# fp.net
KiCad netlist of a schematic drawn in EAGLE
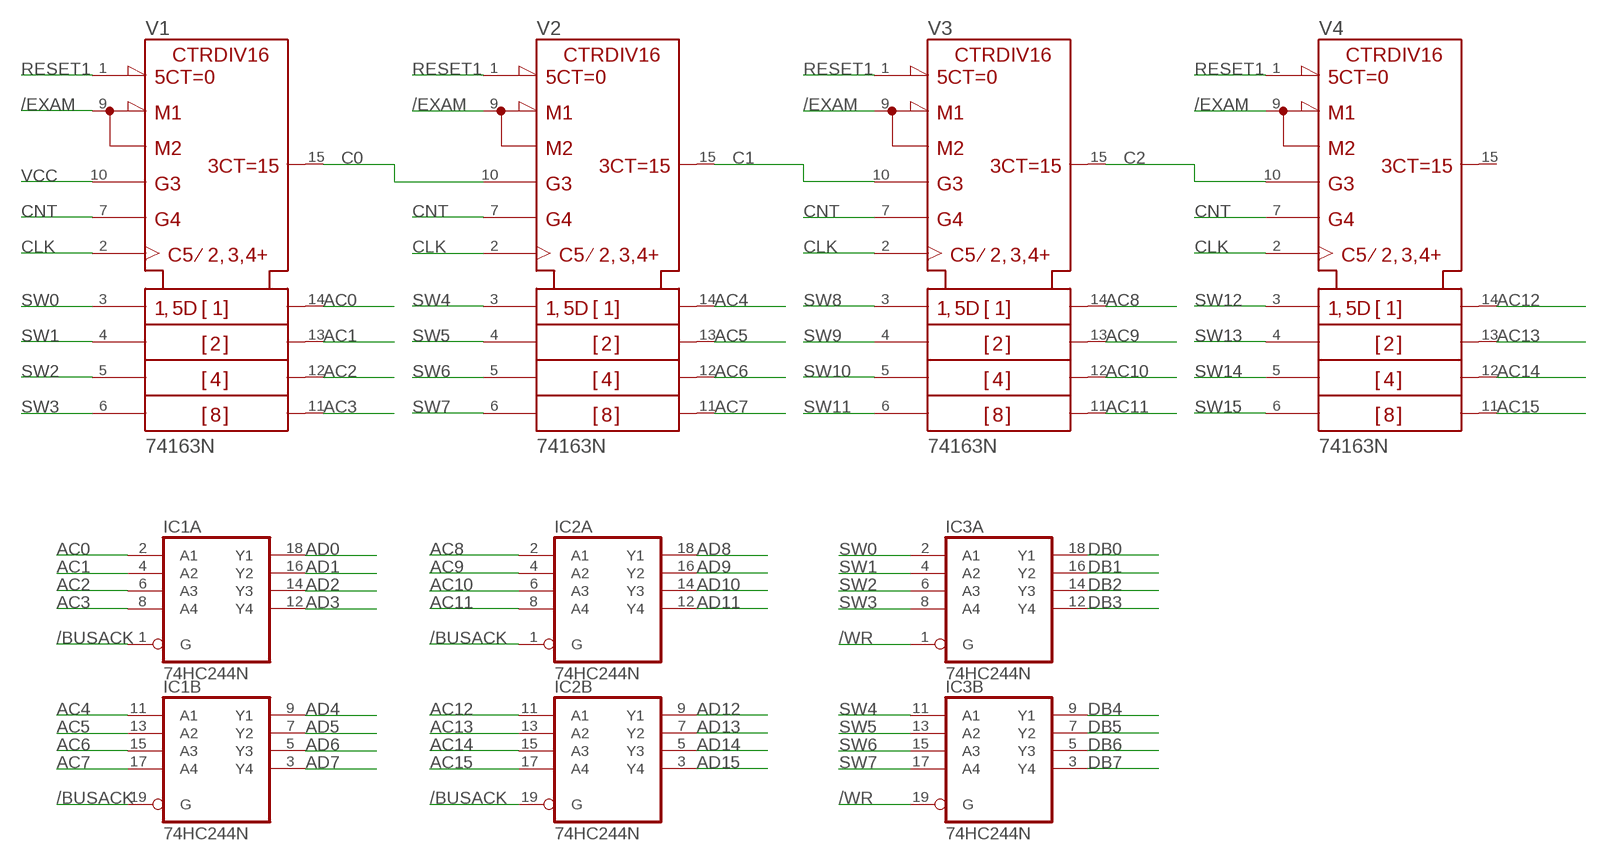
[diagram p0: schematic, sheet 1]

(export (version "E")
  (design (tool "Eeschema 10.0.6"))
  (components
    (comp (ref "IC1")
      (value "74HC244N")
      (footprint "eagle-import:DIL20")
      (libsource (lib "eagle-import") (part "74244NHC"))
    )
    (comp (ref "IC2")
      (value "74HC244N")
      (footprint "eagle-import:DIL20")
      (libsource (lib "eagle-import") (part "74244NHC"))
    )
    (comp (ref "IC3")
      (value "74HC244N")
      (footprint "eagle-import:DIL20")
      (libsource (lib "eagle-import") (part "74244NHC"))
    )
    (comp (ref "V1")
      (value "74163N")
      (footprint "eagle-import:DIL16")
      (libsource (lib "eagle-import") (part "74163N"))
    )
    (comp (ref "V2")
      (value "74163N")
      (footprint "eagle-import:DIL16")
      (libsource (lib "eagle-import") (part "74163N"))
    )
    (comp (ref "V3")
      (value "74163N")
      (footprint "eagle-import:DIL16")
      (libsource (lib "eagle-import") (part "74163N"))
    )
    (comp (ref "V4")
      (value "74163N")
      (footprint "eagle-import:DIL16")
      (libsource (lib "eagle-import") (part "74163N"))
    )
  )
  (nets
    (net (code "1") (name "/AC0") (class "Default")
      (node (ref "IC1") (pin "2") (pinfunction "A1_2") (pintype "input"))
      (node (ref "V1") (pin "14") (pinfunction "QA_14") (pintype "output"))
    )
    (net (code "2") (name "/AC1") (class "Default")
      (node (ref "IC1") (pin "4") (pinfunction "A2_4") (pintype "input"))
      (node (ref "V1") (pin "13") (pinfunction "QB_13") (pintype "output"))
    )
    (net (code "3") (name "/AC2") (class "Default")
      (node (ref "IC1") (pin "6") (pinfunction "A3_6") (pintype "input"))
      (node (ref "V1") (pin "12") (pinfunction "QC_12") (pintype "output"))
    )
    (net (code "4") (name "/AC3") (class "Default")
      (node (ref "IC1") (pin "8") (pinfunction "A4_8") (pintype "input"))
      (node (ref "V1") (pin "11") (pinfunction "QD_11") (pintype "output"))
    )
    (net (code "5") (name "/AC4") (class "Default")
      (node (ref "IC1") (pin "11") (pinfunction "A1_11") (pintype "input"))
      (node (ref "V2") (pin "14") (pinfunction "QA_14") (pintype "output"))
    )
    (net (code "6") (name "/AC5") (class "Default")
      (node (ref "IC1") (pin "13") (pinfunction "A2_13") (pintype "input"))
      (node (ref "V2") (pin "13") (pinfunction "QB_13") (pintype "output"))
    )
    (net (code "7") (name "/AC6") (class "Default")
      (node (ref "IC1") (pin "15") (pinfunction "A3_15") (pintype "input"))
      (node (ref "V2") (pin "12") (pinfunction "QC_12") (pintype "output"))
    )
    (net (code "8") (name "/AC7") (class "Default")
      (node (ref "IC1") (pin "17") (pinfunction "A4_17") (pintype "input"))
      (node (ref "V2") (pin "11") (pinfunction "QD_11") (pintype "output"))
    )
    (net (code "9") (name "/AC8") (class "Default")
      (node (ref "IC2") (pin "2") (pinfunction "A1_2") (pintype "input"))
      (node (ref "V3") (pin "14") (pinfunction "QA_14") (pintype "output"))
    )
    (net (code "10") (name "/AC9") (class "Default")
      (node (ref "IC2") (pin "4") (pinfunction "A2_4") (pintype "input"))
      (node (ref "V3") (pin "13") (pinfunction "QB_13") (pintype "output"))
    )
    (net (code "11") (name "/AC10") (class "Default")
      (node (ref "IC2") (pin "6") (pinfunction "A3_6") (pintype "input"))
      (node (ref "V3") (pin "12") (pinfunction "QC_12") (pintype "output"))
    )
    (net (code "12") (name "/AC11") (class "Default")
      (node (ref "IC2") (pin "8") (pinfunction "A4_8") (pintype "input"))
      (node (ref "V3") (pin "11") (pinfunction "QD_11") (pintype "output"))
    )
    (net (code "13") (name "/AC12") (class "Default")
      (node (ref "IC2") (pin "11") (pinfunction "A1_11") (pintype "input"))
      (node (ref "V4") (pin "14") (pinfunction "QA_14") (pintype "output"))
    )
    (net (code "14") (name "/AC13") (class "Default")
      (node (ref "IC2") (pin "13") (pinfunction "A2_13") (pintype "input"))
      (node (ref "V4") (pin "13") (pinfunction "QB_13") (pintype "output"))
    )
    (net (code "15") (name "/AC14") (class "Default")
      (node (ref "IC2") (pin "15") (pinfunction "A3_15") (pintype "input"))
      (node (ref "V4") (pin "12") (pinfunction "QC_12") (pintype "output"))
    )
    (net (code "16") (name "/AC15") (class "Default")
      (node (ref "IC2") (pin "17") (pinfunction "A4_17") (pintype "input"))
      (node (ref "V4") (pin "11") (pinfunction "QD_11") (pintype "output"))
    )
    (net (code "17") (name "/AD0") (class "Default")
      (node (ref "IC1") (pin "18") (pinfunction "Y1_18") (pintype "tri_state"))
    )
    (net (code "18") (name "/AD1") (class "Default")
      (node (ref "IC1") (pin "16") (pinfunction "Y2_16") (pintype "tri_state"))
    )
    (net (code "19") (name "/AD2") (class "Default")
      (node (ref "IC1") (pin "14") (pinfunction "Y3_14") (pintype "tri_state"))
    )
    (net (code "20") (name "/AD3") (class "Default")
      (node (ref "IC1") (pin "12") (pinfunction "Y4_12") (pintype "tri_state"))
    )
    (net (code "21") (name "/AD4") (class "Default")
      (node (ref "IC1") (pin "9") (pinfunction "Y1_9") (pintype "tri_state"))
    )
    (net (code "22") (name "/AD5") (class "Default")
      (node (ref "IC1") (pin "7") (pinfunction "Y2_7") (pintype "tri_state"))
    )
    (net (code "23") (name "/AD6") (class "Default")
      (node (ref "IC1") (pin "5") (pinfunction "Y3_5") (pintype "tri_state"))
    )
    (net (code "24") (name "/AD7") (class "Default")
      (node (ref "IC1") (pin "3") (pinfunction "Y4_3") (pintype "tri_state"))
    )
    (net (code "25") (name "/AD8") (class "Default")
      (node (ref "IC2") (pin "18") (pinfunction "Y1_18") (pintype "tri_state"))
    )
    (net (code "26") (name "/AD9") (class "Default")
      (node (ref "IC2") (pin "16") (pinfunction "Y2_16") (pintype "tri_state"))
    )
    (net (code "27") (name "/AD10") (class "Default")
      (node (ref "IC2") (pin "14") (pinfunction "Y3_14") (pintype "tri_state"))
    )
    (net (code "28") (name "/AD11") (class "Default")
      (node (ref "IC2") (pin "12") (pinfunction "Y4_12") (pintype "tri_state"))
    )
    (net (code "29") (name "/AD12") (class "Default")
      (node (ref "IC2") (pin "9") (pinfunction "Y1_9") (pintype "tri_state"))
    )
    (net (code "30") (name "/AD13") (class "Default")
      (node (ref "IC2") (pin "7") (pinfunction "Y2_7") (pintype "tri_state"))
    )
    (net (code "31") (name "/AD14") (class "Default")
      (node (ref "IC2") (pin "5") (pinfunction "Y3_5") (pintype "tri_state"))
    )
    (net (code "32") (name "/AD15") (class "Default")
      (node (ref "IC2") (pin "3") (pinfunction "Y4_3") (pintype "tri_state"))
    )
    (net (code "33") (name "/C0") (class "Default")
      (node (ref "V1") (pin "15") (pinfunction "RCO_15") (pintype "output"))
      (node (ref "V2") (pin "10") (pinfunction "ENT_10") (pintype "input"))
    )
    (net (code "34") (name "/C1") (class "Default")
      (node (ref "V2") (pin "15") (pinfunction "RCO_15") (pintype "output"))
      (node (ref "V3") (pin "10") (pinfunction "ENT_10") (pintype "input"))
    )
    (net (code "35") (name "/C2") (class "Default")
      (node (ref "V3") (pin "15") (pinfunction "RCO_15") (pintype "output"))
      (node (ref "V4") (pin "10") (pinfunction "ENT_10") (pintype "input"))
    )
    (net (code "36") (name "/CLK") (class "Default")
      (node (ref "V1") (pin "2") (pinfunction "CLK_2") (pintype "input"))
      (node (ref "V2") (pin "2") (pinfunction "CLK_2") (pintype "input"))
      (node (ref "V3") (pin "2") (pinfunction "CLK_2") (pintype "input"))
      (node (ref "V4") (pin "2") (pinfunction "CLK_2") (pintype "input"))
    )
    (net (code "37") (name "/CNT") (class "Default")
      (node (ref "V1") (pin "7") (pinfunction "ENP_7") (pintype "input"))
      (node (ref "V2") (pin "7") (pinfunction "ENP_7") (pintype "input"))
      (node (ref "V3") (pin "7") (pinfunction "ENP_7") (pintype "input"))
      (node (ref "V4") (pin "7") (pinfunction "ENP_7") (pintype "input"))
    )
    (net (code "38") (name "/DB0") (class "Default")
      (node (ref "IC3") (pin "18") (pinfunction "Y1_18") (pintype "tri_state"))
    )
    (net (code "39") (name "/DB1") (class "Default")
      (node (ref "IC3") (pin "16") (pinfunction "Y2_16") (pintype "tri_state"))
    )
    (net (code "40") (name "/DB2") (class "Default")
      (node (ref "IC3") (pin "14") (pinfunction "Y3_14") (pintype "tri_state"))
    )
    (net (code "41") (name "/DB3") (class "Default")
      (node (ref "IC3") (pin "12") (pinfunction "Y4_12") (pintype "tri_state"))
    )
    (net (code "42") (name "/DB4") (class "Default")
      (node (ref "IC3") (pin "9") (pinfunction "Y1_9") (pintype "tri_state"))
    )
    (net (code "43") (name "/DB5") (class "Default")
      (node (ref "IC3") (pin "7") (pinfunction "Y2_7") (pintype "tri_state"))
    )
    (net (code "44") (name "/DB6") (class "Default")
      (node (ref "IC3") (pin "5") (pinfunction "Y3_5") (pintype "tri_state"))
    )
    (net (code "45") (name "/DB7") (class "Default")
      (node (ref "IC3") (pin "3") (pinfunction "Y4_3") (pintype "tri_state"))
    )
    (net (code "46") (name "/RESET1") (class "Default")
      (node (ref "V1") (pin "1") (pinfunction "~{CLR}_1") (pintype "input"))
      (node (ref "V2") (pin "1") (pinfunction "~{CLR}_1") (pintype "input"))
      (node (ref "V3") (pin "1") (pinfunction "~{CLR}_1") (pintype "input"))
      (node (ref "V4") (pin "1") (pinfunction "~{CLR}_1") (pintype "input"))
    )
    (net (code "47") (name "/SW0") (class "Default")
      (node (ref "IC3") (pin "2") (pinfunction "A1_2") (pintype "input"))
      (node (ref "V1") (pin "3") (pinfunction "A_3") (pintype "input"))
    )
    (net (code "48") (name "/SW1") (class "Default")
      (node (ref "IC3") (pin "4") (pinfunction "A2_4") (pintype "input"))
      (node (ref "V1") (pin "4") (pinfunction "B_4") (pintype "input"))
    )
    (net (code "49") (name "/SW2") (class "Default")
      (node (ref "IC3") (pin "6") (pinfunction "A3_6") (pintype "input"))
      (node (ref "V1") (pin "5") (pinfunction "C_5") (pintype "input"))
    )
    (net (code "50") (name "/SW3") (class "Default")
      (node (ref "IC3") (pin "8") (pinfunction "A4_8") (pintype "input"))
      (node (ref "V1") (pin "6") (pinfunction "D_6") (pintype "input"))
    )
    (net (code "51") (name "/SW4") (class "Default")
      (node (ref "IC3") (pin "11") (pinfunction "A1_11") (pintype "input"))
      (node (ref "V2") (pin "3") (pinfunction "A_3") (pintype "input"))
    )
    (net (code "52") (name "/SW5") (class "Default")
      (node (ref "IC3") (pin "13") (pinfunction "A2_13") (pintype "input"))
      (node (ref "V2") (pin "4") (pinfunction "B_4") (pintype "input"))
    )
    (net (code "53") (name "/SW6") (class "Default")
      (node (ref "IC3") (pin "15") (pinfunction "A3_15") (pintype "input"))
      (node (ref "V2") (pin "5") (pinfunction "C_5") (pintype "input"))
    )
    (net (code "54") (name "/SW7") (class "Default")
      (node (ref "IC3") (pin "17") (pinfunction "A4_17") (pintype "input"))
      (node (ref "V2") (pin "6") (pinfunction "D_6") (pintype "input"))
    )
    (net (code "55") (name "/SW8") (class "Default")
      (node (ref "V3") (pin "3") (pinfunction "A_3") (pintype "input"))
    )
    (net (code "56") (name "/SW9") (class "Default")
      (node (ref "V3") (pin "4") (pinfunction "B_4") (pintype "input"))
    )
    (net (code "57") (name "/SW10") (class "Default")
      (node (ref "V3") (pin "5") (pinfunction "C_5") (pintype "input"))
    )
    (net (code "58") (name "/SW11") (class "Default")
      (node (ref "V3") (pin "6") (pinfunction "D_6") (pintype "input"))
    )
    (net (code "59") (name "/SW12") (class "Default")
      (node (ref "V4") (pin "3") (pinfunction "A_3") (pintype "input"))
    )
    (net (code "60") (name "/SW13") (class "Default")
      (node (ref "V4") (pin "4") (pinfunction "B_4") (pintype "input"))
    )
    (net (code "61") (name "/SW14") (class "Default")
      (node (ref "V4") (pin "5") (pinfunction "C_5") (pintype "input"))
    )
    (net (code "62") (name "/SW15") (class "Default")
      (node (ref "V4") (pin "6") (pinfunction "D_6") (pintype "input"))
    )
    (net (code "63") (name "/VCC") (class "Default")
      (node (ref "V1") (pin "10") (pinfunction "ENT_10") (pintype "input"))
    )
    (net (code "64") (name "/{slash}BUSACK") (class "Default")
      (node (ref "IC1") (pin "1") (pinfunction "G_1") (pintype "input"))
      (node (ref "IC1") (pin "19") (pinfunction "G_19") (pintype "input"))
      (node (ref "IC2") (pin "1") (pinfunction "G_1") (pintype "input"))
      (node (ref "IC2") (pin "19") (pinfunction "G_19") (pintype "input"))
    )
    (net (code "65") (name "/{slash}EXAM") (class "Default")
      (node (ref "V1") (pin "9") (pinfunction "~{LOAD}_9") (pintype "input"))
      (node (ref "V2") (pin "9") (pinfunction "~{LOAD}_9") (pintype "input"))
      (node (ref "V3") (pin "9") (pinfunction "~{LOAD}_9") (pintype "input"))
      (node (ref "V4") (pin "9") (pinfunction "~{LOAD}_9") (pintype "input"))
    )
    (net (code "66") (name "/{slash}WR") (class "Default")
      (node (ref "IC3") (pin "1") (pinfunction "G_1") (pintype "input"))
      (node (ref "IC3") (pin "19") (pinfunction "G_19") (pintype "input"))
    )
    (net (code "67") (name "unconnected-(V4C-RCO-Pad15)") (class "Default")
      (node (ref "V4") (pin "15") (pinfunction "RCO_15") (pintype "output"))
    )
  )
)
